# CCD.net
KiCad netlist of a schematic drawn in Altium Designer
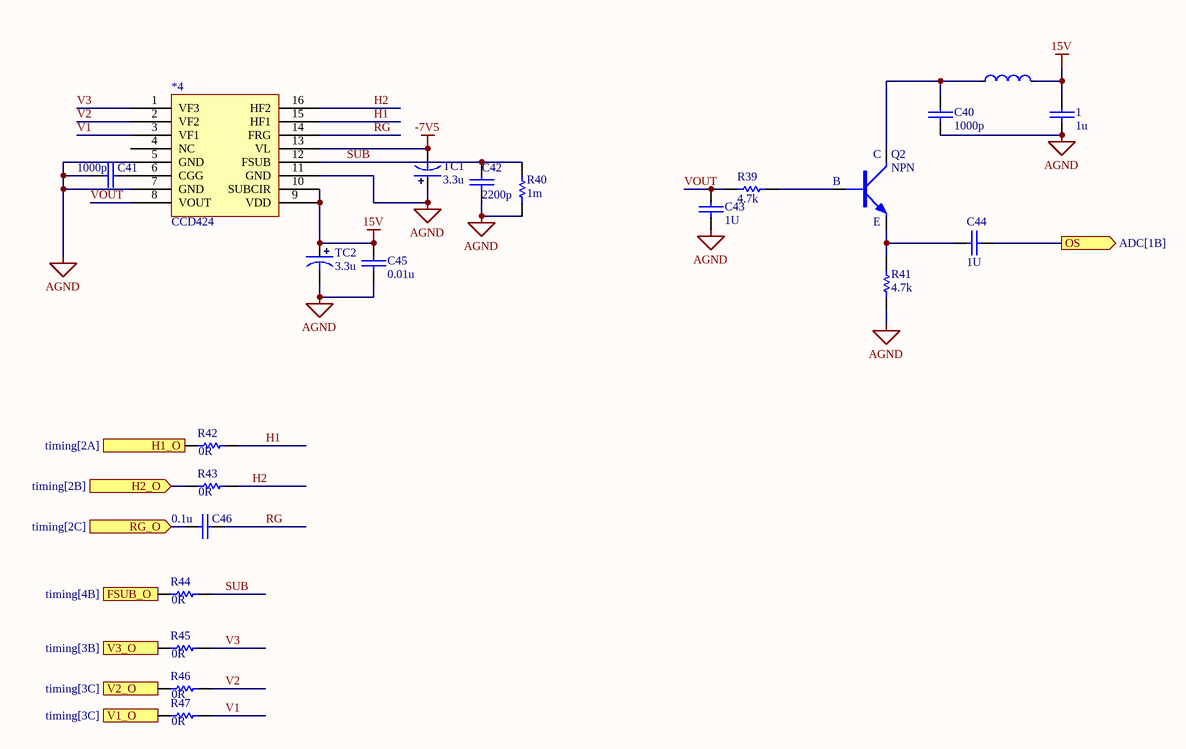
[diagram p0: CCD.SchDoc]

(export (version "E")
  (design (tool "Eeschema 10.0.6"))
  (components
    (comp (ref "*4") (value "CCD424") (footprint "CCD424") (libsource (lib "0.01-CCD") (part "CCD424")))
    (comp (ref "1")
      (value "1u")
      (footprint "0603C")
      (description "无极性电容")
      (libsource (lib "1.00-阻容感") (part "CAP"))
    )
    (comp (ref "C40")
      (value "1000p")
      (footprint "0603C")
      (description "无极性电容")
      (libsource (lib "1.00-阻容感") (part "CAP"))
    )
    (comp (ref "C41")
      (value "1000p")
      (footprint "0603C")
      (description "无极性电容")
      (libsource (lib "1.00-阻容感") (part "CAP"))
    )
    (comp (ref "C42")
      (value "2200p")
      (footprint "0603C")
      (description "无极性电容")
      (libsource (lib "1.00-阻容感") (part "CAP"))
    )
    (comp (ref "C43")
      (value "1U")
      (footprint "0603C")
      (description "无极性电容")
      (libsource (lib "1.00-阻容感") (part "CAP"))
    )
    (comp (ref "C44")
      (value "1U")
      (footprint "0603C")
      (description "无极性电容")
      (libsource (lib "1.00-阻容感") (part "CAP"))
    )
    (comp (ref "C45")
      (value "0.01u")
      (footprint "0603C")
      (description "无极性电容")
      (libsource (lib "1.00-阻容感") (part "CAP"))
    )
    (comp (ref "C46")
      (value "0.1u")
      (footprint "0603C")
      (description "无极性电容")
      (libsource (lib "1.00-阻容感") (part "CAP"))
    )
    (comp (ref "L11")
      (value "GZ1608D601TF")
      (footprint "0603L")
      (description "铁氧体磁珠")
      (fields (field (name "MANUFACTURER") "Sunlord(顺络)") (field (name "TOLERANCE") "±25%"))
      (libsource (lib "1.00-阻容感") (part "FB"))
    )
    (comp (ref "Q2")
      (value "NPN")
      (footprint "SOT23-3")
      (description "NPN三极管")
      (libsource (lib "3.02-三极管") (part "NPN"))
    )
    (comp (ref "R39")
      (value "4.7k")
      (footprint "0603R")
      (description "电阻")
      (libsource (lib "1.00-阻容感") (part "RES"))
    )
    (comp (ref "R40")
      (value "1m")
      (footprint "0603R")
      (description "电阻")
      (libsource (lib "1.00-阻容感") (part "RES"))
    )
    (comp (ref "R41")
      (value "4.7k")
      (footprint "0603R")
      (description "电阻")
      (libsource (lib "1.00-阻容感") (part "RES"))
    )
    (comp (ref "R42")
      (value "0R")
      (footprint "0603R")
      (description "电阻")
      (libsource (lib "1.00-阻容感") (part "RES"))
    )
    (comp (ref "R43")
      (value "0R")
      (footprint "0603R")
      (description "电阻")
      (libsource (lib "1.00-阻容感") (part "RES"))
    )
    (comp (ref "R44")
      (value "0R")
      (footprint "0603R")
      (description "电阻")
      (libsource (lib "1.00-阻容感") (part "RES"))
    )
    (comp (ref "R45")
      (value "0R")
      (footprint "0603R")
      (description "电阻")
      (libsource (lib "1.00-阻容感") (part "RES"))
    )
    (comp (ref "R46")
      (value "0R")
      (footprint "0603R")
      (description "电阻")
      (libsource (lib "1.00-阻容感") (part "RES"))
    )
    (comp (ref "R47")
      (value "0R")
      (footprint "0603R")
      (description "电阻")
      (libsource (lib "1.00-阻容感") (part "RES"))
    )
    (comp (ref "TC1")
      (value "3.3u")
      (footprint "TAJ-A/3216")
      (description "钽电容")
      (libsource (lib "1.00-阻容感") (part "TCAP"))
    )
    (comp (ref "TC2")
      (value "3.3u")
      (footprint "TAJ-A/3216")
      (description "钽电容")
      (libsource (lib "1.00-阻容感") (part "TCAP"))
    )
  )
  (nets
    (net (code "1") (name "-7V5") (class "Default")
      (node (ref "*4") (pin "13") (pinfunction "VL_13") (pintype "passive"))
      (node (ref "TC1") (pin "2") (pinfunction "2_2") (pintype "passive"))
    )
    (net (code "2") (name "/FSUB_O") (class "Default")
      (node (ref "R44") (pin "2") (pinfunction "2_2") (pintype "passive"))
    )
    (net (code "3") (name "/H1") (class "Default")
      (node (ref "*4") (pin "15") (pinfunction "HF1_15") (pintype "passive"))
      (node (ref "R42") (pin "1") (pinfunction "1_1") (pintype "passive"))
    )
    (net (code "4") (name "/H1_O") (class "Default")
      (node (ref "R42") (pin "2") (pinfunction "2_2") (pintype "passive"))
    )
    (net (code "5") (name "/H2") (class "Default")
      (node (ref "*4") (pin "16") (pinfunction "HF2_16") (pintype "passive"))
      (node (ref "R43") (pin "1") (pinfunction "1_1") (pintype "passive"))
    )
    (net (code "6") (name "/H2_O") (class "Default")
      (node (ref "R43") (pin "2") (pinfunction "2_2") (pintype "passive"))
    )
    (net (code "7") (name "/OS") (class "Default")
      (node (ref "C44") (pin "1") (pinfunction "1_1") (pintype "passive"))
    )
    (net (code "8") (name "/RG") (class "Default")
      (node (ref "*4") (pin "14") (pinfunction "FRG_14") (pintype "passive"))
      (node (ref "C46") (pin "1") (pinfunction "1_1") (pintype "passive"))
    )
    (net (code "9") (name "/RG_O") (class "Default")
      (node (ref "C46") (pin "2") (pinfunction "2_2") (pintype "passive"))
    )
    (net (code "10") (name "/SUB") (class "Default")
      (node (ref "*4") (pin "12") (pinfunction "FSUB_12") (pintype "passive"))
      (node (ref "C42") (pin "2") (pinfunction "2_2") (pintype "passive"))
      (node (ref "R40") (pin "2") (pinfunction "2_2") (pintype "passive"))
      (node (ref "R44") (pin "1") (pinfunction "1_1") (pintype "passive"))
    )
    (net (code "11") (name "/V1") (class "Default")
      (node (ref "*4") (pin "3") (pinfunction "VF1_3") (pintype "passive"))
      (node (ref "R47") (pin "1") (pinfunction "1_1") (pintype "passive"))
    )
    (net (code "12") (name "/V1_O") (class "Default")
      (node (ref "R47") (pin "2") (pinfunction "2_2") (pintype "passive"))
    )
    (net (code "13") (name "/V2") (class "Default")
      (node (ref "*4") (pin "2") (pinfunction "VF2_2") (pintype "passive"))
      (node (ref "R46") (pin "1") (pinfunction "1_1") (pintype "passive"))
    )
    (net (code "14") (name "/V2_O") (class "Default")
      (node (ref "R46") (pin "2") (pinfunction "2_2") (pintype "passive"))
    )
    (net (code "15") (name "/V3") (class "Default")
      (node (ref "*4") (pin "1") (pinfunction "VF3_1") (pintype "passive"))
      (node (ref "R45") (pin "1") (pinfunction "1_1") (pintype "passive"))
    )
    (net (code "16") (name "/V3_O") (class "Default")
      (node (ref "R45") (pin "2") (pinfunction "2_2") (pintype "passive"))
    )
    (net (code "17") (name "/VOUT") (class "Default")
      (node (ref "*4") (pin "8") (pinfunction "VOUT_8") (pintype "passive"))
      (node (ref "C43") (pin "1") (pinfunction "1_1") (pintype "passive"))
      (node (ref "R39") (pin "2") (pinfunction "2_2") (pintype "passive"))
    )
    (net (code "18") (name "15V") (class "Default")
      (node (ref "*4") (pin "10") (pinfunction "SUBCIR_10") (pintype "passive"))
      (node (ref "*4") (pin "9") (pinfunction "VDD_9") (pintype "passive"))
      (node (ref "1") (pin "2") (pinfunction "2_2") (pintype "passive"))
      (node (ref "C45") (pin "2") (pinfunction "2_2") (pintype "passive"))
      (node (ref "L11") (pin "2") (pinfunction "2_2") (pintype "passive"))
      (node (ref "TC2") (pin "1") (pinfunction "1_1") (pintype "passive"))
    )
    (net (code "19") (name "AGND") (class "Default")
      (node (ref "*4") (pin "11") (pinfunction "GND_11") (pintype "passive"))
      (node (ref "*4") (pin "5") (pinfunction "GND_5") (pintype "passive"))
      (node (ref "*4") (pin "7") (pinfunction "GND_7") (pintype "passive"))
      (node (ref "1") (pin "1") (pinfunction "1_1") (pintype "passive"))
      (node (ref "C40") (pin "1") (pinfunction "1_1") (pintype "passive"))
      (node (ref "C41") (pin "2") (pinfunction "2_2") (pintype "passive"))
      (node (ref "C42") (pin "1") (pinfunction "1_1") (pintype "passive"))
      (node (ref "C43") (pin "2") (pinfunction "2_2") (pintype "passive"))
      (node (ref "C45") (pin "1") (pinfunction "1_1") (pintype "passive"))
      (node (ref "R40") (pin "1") (pinfunction "1_1") (pintype "passive"))
      (node (ref "R41") (pin "1") (pinfunction "1_1") (pintype "passive"))
      (node (ref "TC1") (pin "1") (pinfunction "1_1") (pintype "passive"))
      (node (ref "TC2") (pin "2") (pinfunction "2_2") (pintype "passive"))
    )
    (net (code "20") (name "Net-(*4-CGG)") (class "Default")
      (node (ref "*4") (pin "6") (pinfunction "CGG_6") (pintype "passive"))
      (node (ref "C41") (pin "1") (pinfunction "1_1") (pintype "passive"))
    )
    (net (code "21") (name "Net-(Q2-B)") (class "Default")
      (node (ref "Q2") (pin "1") (pinfunction "B_1") (pintype "passive"))
      (node (ref "R39") (pin "1") (pinfunction "1_1") (pintype "passive"))
    )
    (net (code "22") (name "Net-(Q2-C)") (class "Default")
      (node (ref "C40") (pin "2") (pinfunction "2_2") (pintype "passive"))
      (node (ref "L11") (pin "1") (pinfunction "1_1") (pintype "passive"))
      (node (ref "Q2") (pin "3") (pinfunction "C_3") (pintype "passive"))
    )
    (net (code "23") (name "Net-(Q2-E)") (class "Default")
      (node (ref "C44") (pin "2") (pinfunction "2_2") (pintype "passive"))
      (node (ref "Q2") (pin "2") (pinfunction "E_2") (pintype "passive"))
      (node (ref "R41") (pin "2") (pinfunction "2_2") (pintype "passive"))
    )
    (net (code "24") (name "unconnected-(*4-NC-Pad4)") (class "Default")
      (node (ref "*4") (pin "4") (pinfunction "NC_4") (pintype "passive"))
    )
  )
)
